# Sequantial_Cell_Switching.net
KiCad netlist of a schematic drawn in Altium Designer
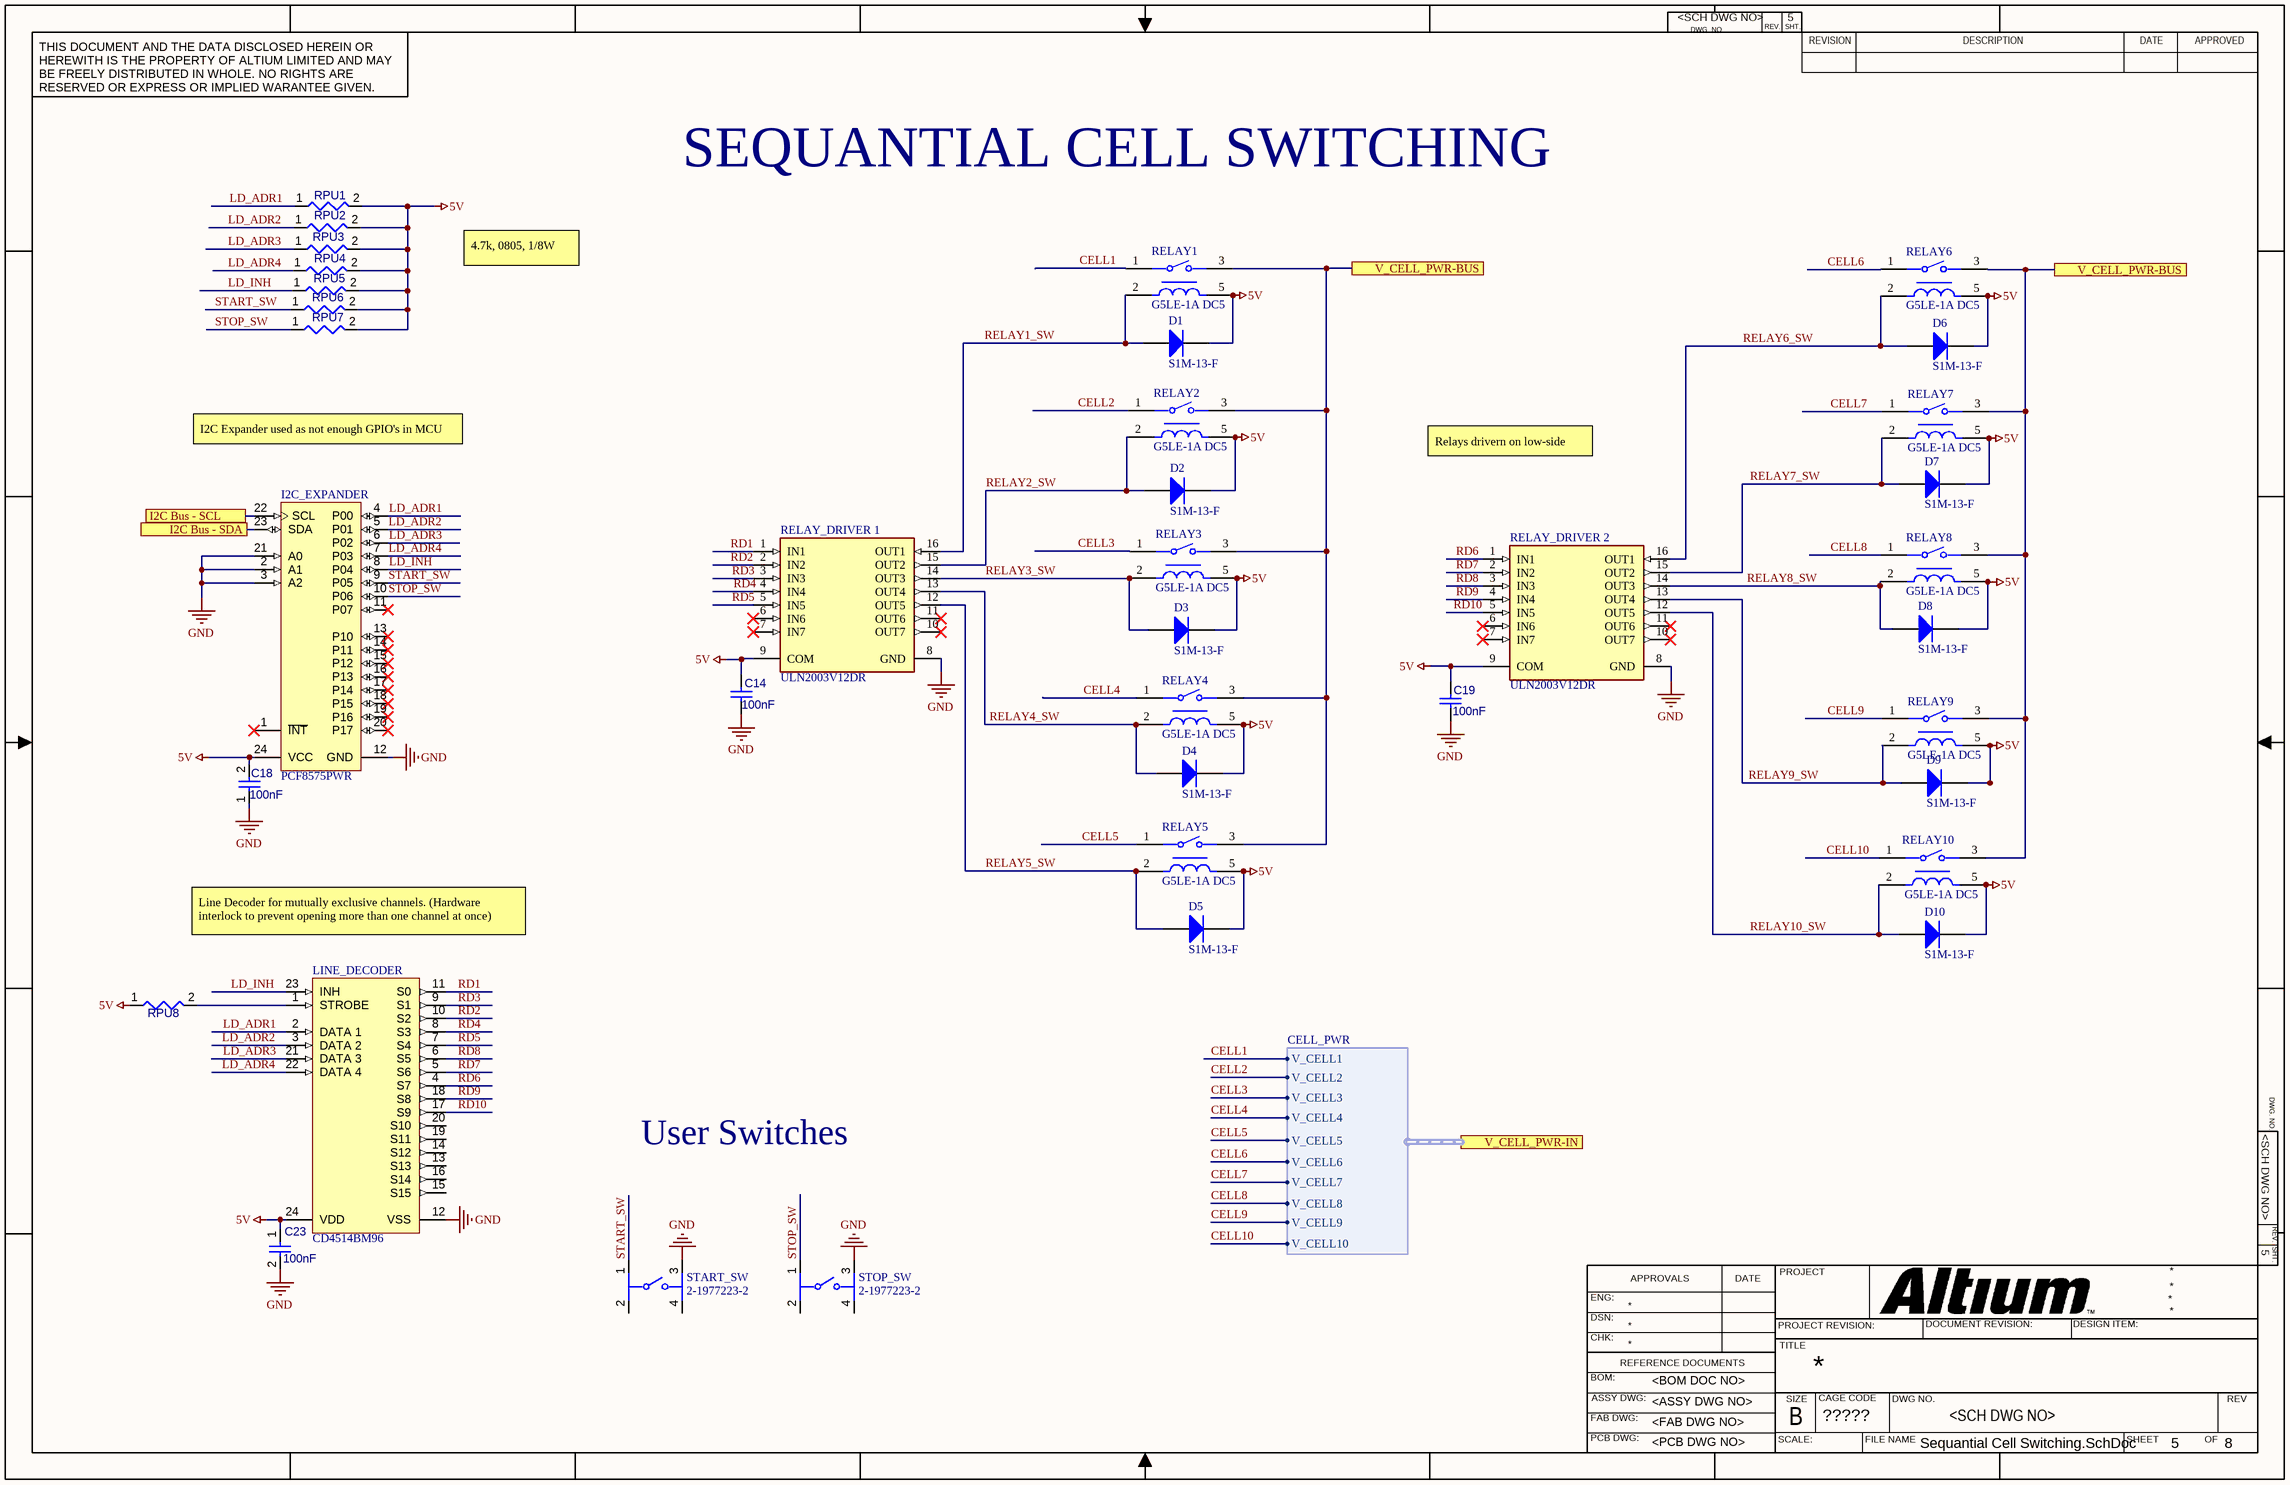
[diagram p0: Sequantial Cell Switching.SchDoc]

(export (version "E")
  (design (tool "Eeschema 10.0.6"))
  (components
    (comp (ref "C14")
      (value "100nF")
      (footprint "CAPC2013X95X50LL10T25")
      (description "Capacitor 100 nF +/-10% 50 V 0805")
      (fields (field (name "TOLERANCE") "10%"))
      (libsource (lib "") (part "CAP-NP-2_1"))
    )
    (comp (ref "C18")
      (value "100nF")
      (footprint "CAPC2013X95X50LL10T25")
      (description "Capacitor 100 nF +/-10% 50 V 0805")
      (fields (field (name "TOLERANCE") "10%"))
      (libsource (lib "gugan Sivakumar") (part "CAP-NP-2"))
    )
    (comp (ref "C19")
      (value "100nF")
      (footprint "CAPC2013X95X50LL10T25")
      (description "Capacitor 100 nF +/-10% 50 V 0805")
      (fields (field (name "TOLERANCE") "10%"))
      (libsource (lib "") (part "CAP-NP-2_1"))
    )
    (comp (ref "C23")
      (value "100nF")
      (footprint "CAPC2013X95X50LL10T25")
      (description "Capacitor 100 nF +/-10% 50 V 0805")
      (fields (field (name "TOLERANCE") "10%"))
      (libsource (lib "gugan Sivakumar") (part "CAP-NP-2"))
    )
    (comp (ref "D1")
      (value "S1M-13-F")
      (footprint "DIOD-S1M-13-F-SMA-2_V")
      (fields (field (name "MANUFACTURER") "Diodes Inc"))
      (libsource (lib "Altium Content Vault") (part "DIOD-D-A1K2-2"))
    )
    (comp (ref "D2")
      (value "S1M-13-F")
      (footprint "DIOD-S1M-13-F-SMA-2_V")
      (fields (field (name "MANUFACTURER") "Diodes Inc"))
      (libsource (lib "Altium Content Vault") (part "DIOD-D-A1K2-2"))
    )
    (comp (ref "D3")
      (value "S1M-13-F")
      (footprint "DIOD-S1M-13-F-SMA-2_V")
      (fields (field (name "MANUFACTURER") "Diodes Inc"))
      (libsource (lib "Altium Content Vault") (part "DIOD-D-A1K2-2"))
    )
    (comp (ref "D4")
      (value "S1M-13-F")
      (footprint "DIOD-S1M-13-F-SMA-2_V")
      (fields (field (name "MANUFACTURER") "Diodes Inc"))
      (libsource (lib "Altium Content Vault") (part "DIOD-D-A1K2-2"))
    )
    (comp (ref "D5")
      (value "S1M-13-F")
      (footprint "DIOD-S1M-13-F-SMA-2_V")
      (fields (field (name "MANUFACTURER") "Diodes Inc"))
      (libsource (lib "Altium Content Vault") (part "DIOD-D-A1K2-2"))
    )
    (comp (ref "D6")
      (value "S1M-13-F")
      (footprint "DIOD-S1M-13-F-SMA-2_V")
      (fields (field (name "MANUFACTURER") "Diodes Inc"))
      (libsource (lib "Altium Content Vault") (part "DIOD-D-A1K2-2"))
    )
    (comp (ref "D7")
      (value "S1M-13-F")
      (footprint "DIOD-S1M-13-F-SMA-2_V")
      (fields (field (name "MANUFACTURER") "Diodes Inc"))
      (libsource (lib "Altium Content Vault") (part "DIOD-D-A1K2-2"))
    )
    (comp (ref "D8")
      (value "S1M-13-F")
      (footprint "DIOD-S1M-13-F-SMA-2_V")
      (fields (field (name "MANUFACTURER") "Diodes Inc"))
      (libsource (lib "Altium Content Vault") (part "DIOD-D-A1K2-2"))
    )
    (comp (ref "D9")
      (value "S1M-13-F")
      (footprint "DIOD-S1M-13-F-SMA-2_V")
      (fields (field (name "MANUFACTURER") "Diodes Inc"))
      (libsource (lib "Altium Content Vault") (part "DIOD-D-A1K2-2"))
    )
    (comp (ref "D10")
      (value "S1M-13-F")
      (footprint "DIOD-S1M-13-F-SMA-2_V")
      (fields (field (name "MANUFACTURER") "Diodes Inc"))
      (libsource (lib "Altium Content Vault") (part "DIOD-D-A1K2-2"))
    )
    (comp (ref "I2C_EXPANDER")
      (value "PCF8575PWR")
      (footprint "PW0024A_L")
      (fields (field (name "MANUFACTURER") "Texas Instruments"))
      (libsource (lib "Altium Content Vault") (part "TI-PCF8575-TSSOP_PW-24"))
    )
    (comp (ref "LINE_DECODER")
      (value "CD4514BM96")
      (footprint "DW0024A_N")
      (description "CMOS 4-Bit Latch/4-to-16 Line Decoder with Output 'High' on Select, DW0024A, LARGE T&R")
      (fields
        (field (name "GENERIC PART NUMBER") "CD4514B")
        (field (name "MANUFACTURER") "Texas Instruments")
      )
      (libsource (lib "Altium Content Vault") (part "TI-CD451XB-24"))
    )
    (comp (ref "RELAY1")
      (value "G5LE-1A DC5")
      (footprint "FP-G5LE-1A_DC5-MFG")
      (description "RELAY GEN PURPOSE SPST 10A 5V")
      (libsource (lib "Altium Content Vault") (part "6e495d724dc645a58f977e2129b87ff"))
    )
    (comp (ref "RELAY2")
      (value "G5LE-1A DC5")
      (footprint "FP-G5LE-1A_DC5-MFG")
      (description "RELAY GEN PURPOSE SPST 10A 5V")
      (libsource (lib "Altium Content Vault") (part "6e495d724dc645a58f977e2129b87ff"))
    )
    (comp (ref "RELAY3")
      (value "G5LE-1A DC5")
      (footprint "FP-G5LE-1A_DC5-MFG")
      (description "RELAY GEN PURPOSE SPST 10A 5V")
      (libsource (lib "Altium Content Vault") (part "6e495d724dc645a58f977e2129b87ff"))
    )
    (comp (ref "RELAY4")
      (value "G5LE-1A DC5")
      (footprint "FP-G5LE-1A_DC5-MFG")
      (description "RELAY GEN PURPOSE SPST 10A 5V")
      (libsource (lib "Altium Content Vault") (part "6e495d724dc645a58f977e2129b87ff"))
    )
    (comp (ref "RELAY5")
      (value "G5LE-1A DC5")
      (footprint "FP-G5LE-1A_DC5-MFG")
      (description "RELAY GEN PURPOSE SPST 10A 5V")
      (libsource (lib "Altium Content Vault") (part "6e495d724dc645a58f977e2129b87ff"))
    )
    (comp (ref "RELAY6")
      (value "G5LE-1A DC5")
      (footprint "FP-G5LE-1A_DC5-MFG")
      (description "RELAY GEN PURPOSE SPST 10A 5V")
      (libsource (lib "Altium Content Vault") (part "6e495d724dc645a58f977e2129b87ff"))
    )
    (comp (ref "RELAY7")
      (value "G5LE-1A DC5")
      (footprint "FP-G5LE-1A_DC5-MFG")
      (description "RELAY GEN PURPOSE SPST 10A 5V")
      (libsource (lib "Altium Content Vault") (part "6e495d724dc645a58f977e2129b87ff"))
    )
    (comp (ref "RELAY8")
      (value "G5LE-1A DC5")
      (footprint "FP-G5LE-1A_DC5-MFG")
      (description "RELAY GEN PURPOSE SPST 10A 5V")
      (libsource (lib "Altium Content Vault") (part "6e495d724dc645a58f977e2129b87ff"))
    )
    (comp (ref "RELAY9")
      (value "G5LE-1A DC5")
      (footprint "FP-G5LE-1A_DC5-MFG")
      (description "RELAY GEN PURPOSE SPST 10A 5V")
      (libsource (lib "Altium Content Vault") (part "6e495d724dc645a58f977e2129b87ff"))
    )
    (comp (ref "RELAY10")
      (value "G5LE-1A DC5")
      (footprint "FP-G5LE-1A_DC5-MFG")
      (description "RELAY GEN PURPOSE SPST 10A 5V")
      (libsource (lib "Altium Content Vault") (part "6e495d724dc645a58f977e2129b87ff"))
    )
    (comp (ref "RELAY_DRIVER 1")
      (value "ULN2003V12DR")
      (footprint "FP-D0016A-MFG")
      (description "MOSFET 7CH 16SOIC")
      (libsource (lib "Altium Content Vault") (part "1bf5c18f3aeaca83cb90dec63c1b343"))
    )
    (comp (ref "RELAY_DRIVER 2")
      (value "ULN2003V12DR")
      (footprint "FP-D0016A-MFG")
      (description "MOSFET 7CH 16SOIC")
      (libsource (lib "Altium Content Vault") (part "1bf5c18f3aeaca83cb90dec63c1b343"))
    )
    (comp (ref "RPU1")
      (value "Resistor 4k7 +/-1% 0805 125 mW")
      (footprint "RESC2013X70X40ML20T20")
      (description "Chip Resistor, 4.7 KOhm, +/- 1%, 0.125 W, -55 to 155 degC, 0805 (2012 Metric)")
      (fields (field (name "TOLERANCE") "1%") (field (name "POWER") "125mW"))
      (libsource (lib "gugan Sivakumar") (part "RES-2"))
    )
    (comp (ref "RPU2")
      (value "Resistor 4k7 +/-1% 0805 125 mW")
      (footprint "RESC2013X70X40ML20T20")
      (description "Chip Resistor, 4.7 KOhm, +/- 1%, 0.125 W, -55 to 155 degC, 0805 (2012 Metric)")
      (fields (field (name "TOLERANCE") "1%") (field (name "POWER") "125mW"))
      (libsource (lib "gugan Sivakumar") (part "RES-2"))
    )
    (comp (ref "RPU3")
      (value "Resistor 4k7 +/-1% 0805 125 mW")
      (footprint "RESC2013X70X40ML20T20")
      (description "Chip Resistor, 4.7 KOhm, +/- 1%, 0.125 W, -55 to 155 degC, 0805 (2012 Metric)")
      (fields (field (name "TOLERANCE") "1%") (field (name "POWER") "125mW"))
      (libsource (lib "gugan Sivakumar") (part "RES-2"))
    )
    (comp (ref "RPU4")
      (value "Resistor 4k7 +/-1% 0805 125 mW")
      (footprint "RESC2013X70X40ML20T20")
      (description "Chip Resistor, 4.7 KOhm, +/- 1%, 0.125 W, -55 to 155 degC, 0805 (2012 Metric)")
      (fields (field (name "TOLERANCE") "1%") (field (name "POWER") "125mW"))
      (libsource (lib "gugan Sivakumar") (part "RES-2"))
    )
    (comp (ref "RPU5")
      (value "Resistor 4k7 +/-1% 0805 125 mW")
      (footprint "RESC2013X70X40ML20T20")
      (description "Chip Resistor, 4.7 KOhm, +/- 1%, 0.125 W, -55 to 155 degC, 0805 (2012 Metric)")
      (fields (field (name "TOLERANCE") "1%") (field (name "POWER") "125mW"))
      (libsource (lib "gugan Sivakumar") (part "RES-2"))
    )
    (comp (ref "RPU6")
      (value "Resistor 4k7 +/-1% 0805 125 mW")
      (footprint "RESC2013X70X40ML20T20")
      (description "Chip Resistor, 4.7 KOhm, +/- 1%, 0.125 W, -55 to 155 degC, 0805 (2012 Metric)")
      (fields (field (name "TOLERANCE") "1%") (field (name "POWER") "125mW"))
      (libsource (lib "gugan Sivakumar") (part "RES-2"))
    )
    (comp (ref "RPU7")
      (value "Resistor 4k7 +/-1% 0805 125 mW")
      (footprint "RESC2013X70X40ML20T20")
      (description "Chip Resistor, 4.7 KOhm, +/- 1%, 0.125 W, -55 to 155 degC, 0805 (2012 Metric)")
      (fields (field (name "TOLERANCE") "1%") (field (name "POWER") "125mW"))
      (libsource (lib "gugan Sivakumar") (part "RES-2"))
    )
    (comp (ref "RPU8")
      (value "Resistor 4k7 +/-1% 0805 125 mW")
      (footprint "RESC2013X70X40ML20T20")
      (description "Chip Resistor, 4.7 KOhm, +/- 1%, 0.125 W, -55 to 155 degC, 0805 (2012 Metric)")
      (fields (field (name "TOLERANCE") "1%") (field (name "POWER") "125mW"))
      (libsource (lib "gugan Sivakumar") (part "RES-2"))
    )
    (comp (ref "START_SW")
      (value "2-1977223-2")
      (footprint "FP-2-1977223-2-MFG")
      (description "SWITCH TACTILE SPST-NO 0.05A 24V")
      (libsource (lib "Altium Content Vault") (part "b8895f3f4cefb76e1819d2863dba89b"))
    )
    (comp (ref "STOP_SW")
      (value "2-1977223-2")
      (footprint "FP-2-1977223-2-MFG")
      (description "SWITCH TACTILE SPST-NO 0.05A 24V")
      (libsource (lib "Altium Content Vault") (part "b8895f3f4cefb76e1819d2863dba89b"))
    )
  )
  (nets
    (net (code "2") (name "/CELL1") (class "Default")
      (node (ref "RELAY1") (pin "1") (pinfunction "1_1") (pintype "passive"))
    )
    (net (code "3") (name "/CELL2") (class "Default")
      (node (ref "RELAY2") (pin "1") (pinfunction "1_1") (pintype "passive"))
    )
    (net (code "4") (name "/CELL3") (class "Default")
      (node (ref "RELAY3") (pin "1") (pinfunction "1_1") (pintype "passive"))
    )
    (net (code "5") (name "/CELL4") (class "Default")
      (node (ref "RELAY4") (pin "1") (pinfunction "1_1") (pintype "passive"))
    )
    (net (code "6") (name "/CELL5") (class "Default")
      (node (ref "RELAY5") (pin "1") (pinfunction "1_1") (pintype "passive"))
    )
    (net (code "7") (name "/CELL6") (class "Default")
      (node (ref "RELAY6") (pin "1") (pinfunction "1_1") (pintype "passive"))
    )
    (net (code "8") (name "/CELL7") (class "Default")
      (node (ref "RELAY7") (pin "1") (pinfunction "1_1") (pintype "passive"))
    )
    (net (code "9") (name "/CELL8") (class "Default")
      (node (ref "RELAY8") (pin "1") (pinfunction "1_1") (pintype "passive"))
    )
    (net (code "10") (name "/CELL9") (class "Default")
      (node (ref "RELAY9") (pin "1") (pinfunction "1_1") (pintype "passive"))
    )
    (net (code "11") (name "/CELL10") (class "Default")
      (node (ref "RELAY10") (pin "1") (pinfunction "1_1") (pintype "passive"))
    )
    (net (code "12") (name "/I2C Bus - SCL") (class "Default")
      (node (ref "I2C_EXPANDER") (pin "22") (pinfunction "SCL_22") (pintype "input"))
    )
    (net (code "13") (name "/I2C Bus - SDA") (class "Default")
      (node (ref "I2C_EXPANDER") (pin "23") (pinfunction "SDA_23") (pintype "bidirectional"))
    )
    (net (code "14") (name "/LD_ADR1") (class "Default")
      (node (ref "I2C_EXPANDER") (pin "4") (pinfunction "P00_4") (pintype "bidirectional"))
      (node (ref "LINE_DECODER") (pin "2") (pinfunction "DATA_1_2") (pintype "input"))
      (node (ref "RPU1") (pin "1") (pinfunction "1_1") (pintype "passive"))
    )
    (net (code "15") (name "/LD_ADR2") (class "Default")
      (node (ref "I2C_EXPANDER") (pin "5") (pinfunction "P01_5") (pintype "bidirectional"))
      (node (ref "LINE_DECODER") (pin "3") (pinfunction "DATA_2_3") (pintype "input"))
      (node (ref "RPU2") (pin "1") (pinfunction "1_1") (pintype "passive"))
    )
    (net (code "16") (name "/LD_ADR3") (class "Default")
      (node (ref "I2C_EXPANDER") (pin "6") (pinfunction "P02_6") (pintype "bidirectional"))
      (node (ref "LINE_DECODER") (pin "21") (pinfunction "DATA_3_21") (pintype "input"))
      (node (ref "RPU3") (pin "1") (pinfunction "1_1") (pintype "passive"))
    )
    (net (code "17") (name "/LD_ADR4") (class "Default")
      (node (ref "I2C_EXPANDER") (pin "7") (pinfunction "P03_7") (pintype "bidirectional"))
      (node (ref "LINE_DECODER") (pin "22") (pinfunction "DATA_4_22") (pintype "input"))
      (node (ref "RPU4") (pin "1") (pinfunction "1_1") (pintype "passive"))
    )
    (net (code "18") (name "/LD_INH") (class "Default")
      (node (ref "I2C_EXPANDER") (pin "8") (pinfunction "P04_8") (pintype "bidirectional"))
      (node (ref "LINE_DECODER") (pin "23") (pinfunction "INH_23") (pintype "input"))
      (node (ref "RPU5") (pin "1") (pinfunction "1_1") (pintype "passive"))
    )
    (net (code "19") (name "/RD1") (class "Default")
      (node (ref "LINE_DECODER") (pin "11") (pinfunction "S0_11") (pintype "output"))
      (node (ref "RELAY_DRIVER 1") (pin "1") (pinfunction "IN1_1") (pintype "input"))
    )
    (net (code "20") (name "/RD2") (class "Default")
      (node (ref "LINE_DECODER") (pin "10") (pinfunction "S2_10") (pintype "output"))
      (node (ref "RELAY_DRIVER 1") (pin "2") (pinfunction "IN2_2") (pintype "input"))
    )
    (net (code "21") (name "/RD3") (class "Default")
      (node (ref "LINE_DECODER") (pin "9") (pinfunction "S1_9") (pintype "output"))
      (node (ref "RELAY_DRIVER 1") (pin "3") (pinfunction "IN3_3") (pintype "input"))
    )
    (net (code "22") (name "/RD4") (class "Default")
      (node (ref "LINE_DECODER") (pin "8") (pinfunction "S3_8") (pintype "output"))
      (node (ref "RELAY_DRIVER 1") (pin "4") (pinfunction "IN4_4") (pintype "input"))
    )
    (net (code "23") (name "/RD5") (class "Default")
      (node (ref "LINE_DECODER") (pin "7") (pinfunction "S4_7") (pintype "output"))
      (node (ref "RELAY_DRIVER 1") (pin "5") (pinfunction "IN5_5") (pintype "input"))
    )
    (net (code "24") (name "/RD6") (class "Default")
      (node (ref "LINE_DECODER") (pin "4") (pinfunction "S7_4") (pintype "output"))
      (node (ref "RELAY_DRIVER 2") (pin "1") (pinfunction "IN1_1") (pintype "input"))
    )
    (net (code "25") (name "/RD7") (class "Default")
      (node (ref "LINE_DECODER") (pin "5") (pinfunction "S6_5") (pintype "output"))
      (node (ref "RELAY_DRIVER 2") (pin "2") (pinfunction "IN2_2") (pintype "input"))
    )
    (net (code "26") (name "/RD8") (class "Default")
      (node (ref "LINE_DECODER") (pin "6") (pinfunction "S5_6") (pintype "output"))
      (node (ref "RELAY_DRIVER 2") (pin "3") (pinfunction "IN3_3") (pintype "input"))
    )
    (net (code "27") (name "/RD9") (class "Default")
      (node (ref "LINE_DECODER") (pin "18") (pinfunction "S8_18") (pintype "output"))
      (node (ref "RELAY_DRIVER 2") (pin "4") (pinfunction "IN4_4") (pintype "input"))
    )
    (net (code "28") (name "/RD10") (class "Default")
      (node (ref "LINE_DECODER") (pin "17") (pinfunction "S9_17") (pintype "output"))
      (node (ref "RELAY_DRIVER 2") (pin "5") (pinfunction "IN5_5") (pintype "input"))
    )
    (net (code "29") (name "/RELAY1_SW") (class "Default")
      (node (ref "D1") (pin "1") (pinfunction "A_1") (pintype "passive"))
      (node (ref "RELAY1") (pin "2") (pinfunction "2_2") (pintype "passive"))
      (node (ref "RELAY_DRIVER 1") (pin "16") (pinfunction "OUT1_16") (pintype "input"))
    )
    (net (code "30") (name "/RELAY2_SW") (class "Default")
      (node (ref "D2") (pin "1") (pinfunction "A_1") (pintype "passive"))
      (node (ref "RELAY2") (pin "2") (pinfunction "2_2") (pintype "passive"))
      (node (ref "RELAY_DRIVER 1") (pin "15") (pinfunction "OUT2_15") (pintype "output"))
    )
    (net (code "31") (name "/RELAY3_SW") (class "Default")
      (node (ref "D3") (pin "1") (pinfunction "A_1") (pintype "passive"))
      (node (ref "RELAY3") (pin "2") (pinfunction "2_2") (pintype "passive"))
      (node (ref "RELAY_DRIVER 1") (pin "14") (pinfunction "OUT3_14") (pintype "output"))
    )
    (net (code "32") (name "/RELAY4_SW") (class "Default")
      (node (ref "D4") (pin "1") (pinfunction "A_1") (pintype "passive"))
      (node (ref "RELAY4") (pin "2") (pinfunction "2_2") (pintype "passive"))
      (node (ref "RELAY_DRIVER 1") (pin "13") (pinfunction "OUT4_13") (pintype "output"))
    )
    (net (code "33") (name "/RELAY5_SW") (class "Default")
      (node (ref "D5") (pin "1") (pinfunction "A_1") (pintype "passive"))
      (node (ref "RELAY5") (pin "2") (pinfunction "2_2") (pintype "passive"))
      (node (ref "RELAY_DRIVER 1") (pin "12") (pinfunction "OUT5_12") (pintype "output"))
    )
    (net (code "34") (name "/RELAY6_SW") (class "Default")
      (node (ref "D6") (pin "1") (pinfunction "A_1") (pintype "passive"))
      (node (ref "RELAY6") (pin "2") (pinfunction "2_2") (pintype "passive"))
      (node (ref "RELAY_DRIVER 2") (pin "16") (pinfunction "OUT1_16") (pintype "input"))
    )
    (net (code "35") (name "/RELAY7_SW") (class "Default")
      (node (ref "D7") (pin "1") (pinfunction "A_1") (pintype "passive"))
      (node (ref "RELAY7") (pin "2") (pinfunction "2_2") (pintype "passive"))
      (node (ref "RELAY_DRIVER 2") (pin "15") (pinfunction "OUT2_15") (pintype "output"))
    )
    (net (code "36") (name "/RELAY8_SW") (class "Default")
      (node (ref "D8") (pin "1") (pinfunction "A_1") (pintype "passive"))
      (node (ref "RELAY8") (pin "2") (pinfunction "2_2") (pintype "passive"))
      (node (ref "RELAY_DRIVER 2") (pin "14") (pinfunction "OUT3_14") (pintype "output"))
    )
    (net (code "37") (name "/RELAY9_SW") (class "Default")
      (node (ref "D9") (pin "1") (pinfunction "A_1") (pintype "passive"))
      (node (ref "RELAY9") (pin "2") (pinfunction "2_2") (pintype "passive"))
      (node (ref "RELAY_DRIVER 2") (pin "13") (pinfunction "OUT4_13") (pintype "output"))
    )
    (net (code "38") (name "/RELAY10_SW") (class "Default")
      (node (ref "D10") (pin "1") (pinfunction "A_1") (pintype "passive"))
      (node (ref "RELAY10") (pin "2") (pinfunction "2_2") (pintype "passive"))
      (node (ref "RELAY_DRIVER 2") (pin "12") (pinfunction "OUT5_12") (pintype "output"))
    )
    (net (code "39") (name "/START_SW") (class "Default")
      (node (ref "I2C_EXPANDER") (pin "9") (pinfunction "P05_9") (pintype "bidirectional"))
      (node (ref "RPU6") (pin "1") (pinfunction "1_1") (pintype "passive"))
      (node (ref "START_SW") (pin "1") (pinfunction "1_1") (pintype "passive"))
    )
    (net (code "40") (name "/STOP_SW") (class "Default")
      (node (ref "I2C_EXPANDER") (pin "10") (pinfunction "P06_10") (pintype "bidirectional"))
      (node (ref "RPU7") (pin "1") (pinfunction "1_1") (pintype "passive"))
      (node (ref "STOP_SW") (pin "1") (pinfunction "1_1") (pintype "passive"))
    )
    (net (code "41") (name "/V_CELL_PWR-BUS") (class "Default")
      (node (ref "RELAY1") (pin "3") (pinfunction "3_3") (pintype "passive"))
      (node (ref "RELAY10") (pin "3") (pinfunction "3_3") (pintype "passive"))
      (node (ref "RELAY2") (pin "3") (pinfunction "3_3") (pintype "passive"))
      (node (ref "RELAY3") (pin "3") (pinfunction "3_3") (pintype "passive"))
      (node (ref "RELAY4") (pin "3") (pinfunction "3_3") (pintype "passive"))
      (node (ref "RELAY5") (pin "3") (pinfunction "3_3") (pintype "passive"))
      (node (ref "RELAY6") (pin "3") (pinfunction "3_3") (pintype "passive"))
      (node (ref "RELAY7") (pin "3") (pinfunction "3_3") (pintype "passive"))
      (node (ref "RELAY8") (pin "3") (pinfunction "3_3") (pintype "passive"))
      (node (ref "RELAY9") (pin "3") (pinfunction "3_3") (pintype "passive"))
    )
    (net (code "43") (name "5V") (class "Default")
      (node (ref "C14") (pin "2") (pinfunction "2_2") (pintype "passive"))
      (node (ref "C18") (pin "2") (pinfunction "2_2") (pintype "passive"))
      (node (ref "C19") (pin "2") (pinfunction "2_2") (pintype "passive"))
      (node (ref "C23") (pin "1") (pinfunction "1_1") (pintype "passive"))
      (node (ref "D1") (pin "2") (pinfunction "K_2") (pintype "passive"))
      (node (ref "D10") (pin "2") (pinfunction "K_2") (pintype "passive"))
      (node (ref "D2") (pin "2") (pinfunction "K_2") (pintype "passive"))
      (node (ref "D3") (pin "2") (pinfunction "K_2") (pintype "passive"))
      (node (ref "D4") (pin "2") (pinfunction "K_2") (pintype "passive"))
      (node (ref "D5") (pin "2") (pinfunction "K_2") (pintype "passive"))
      (node (ref "D6") (pin "2") (pinfunction "K_2") (pintype "passive"))
      (node (ref "D7") (pin "2") (pinfunction "K_2") (pintype "passive"))
      (node (ref "D8") (pin "2") (pinfunction "K_2") (pintype "passive"))
      (node (ref "D9") (pin "2") (pinfunction "K_2") (pintype "passive"))
      (node (ref "I2C_EXPANDER") (pin "24") (pinfunction "VCC_24") (pintype "power_in"))
      (node (ref "LINE_DECODER") (pin "24") (pinfunction "VDD_24") (pintype "power_in"))
      (node (ref "RELAY1") (pin "5") (pinfunction "5_5") (pintype "passive"))
      (node (ref "RELAY10") (pin "5") (pinfunction "5_5") (pintype "passive"))
      (node (ref "RELAY2") (pin "5") (pinfunction "5_5") (pintype "passive"))
      (node (ref "RELAY3") (pin "5") (pinfunction "5_5") (pintype "passive"))
      (node (ref "RELAY4") (pin "5") (pinfunction "5_5") (pintype "passive"))
      (node (ref "RELAY5") (pin "5") (pinfunction "5_5") (pintype "passive"))
      (node (ref "RELAY6") (pin "5") (pinfunction "5_5") (pintype "passive"))
      (node (ref "RELAY7") (pin "5") (pinfunction "5_5") (pintype "passive"))
      (node (ref "RELAY8") (pin "5") (pinfunction "5_5") (pintype "passive"))
      (node (ref "RELAY9") (pin "5") (pinfunction "5_5") (pintype "passive"))
      (node (ref "RELAY_DRIVER 1") (pin "9") (pinfunction "COM_9") (pintype "passive"))
      (node (ref "RELAY_DRIVER 2") (pin "9") (pinfunction "COM_9") (pintype "passive"))
      (node (ref "RPU1") (pin "2") (pinfunction "2_2") (pintype "passive"))
      (node (ref "RPU2") (pin "2") (pinfunction "2_2") (pintype "passive"))
      (node (ref "RPU3") (pin "2") (pinfunction "2_2") (pintype "passive"))
      (node (ref "RPU4") (pin "2") (pinfunction "2_2") (pintype "passive"))
      (node (ref "RPU5") (pin "2") (pinfunction "2_2") (pintype "passive"))
      (node (ref "RPU6") (pin "2") (pinfunction "2_2") (pintype "passive"))
      (node (ref "RPU7") (pin "2") (pinfunction "2_2") (pintype "passive"))
      (node (ref "RPU8") (pin "1") (pinfunction "1_1") (pintype "passive"))
    )
    (net (code "44") (name "GND") (class "Default")
      (node (ref "C14") (pin "1") (pinfunction "1_1") (pintype "passive"))
      (node (ref "C18") (pin "1") (pinfunction "1_1") (pintype "passive"))
      (node (ref "C19") (pin "1") (pinfunction "1_1") (pintype "passive"))
      (node (ref "C23") (pin "2") (pinfunction "2_2") (pintype "passive"))
      (node (ref "I2C_EXPANDER") (pin "12") (pinfunction "GND_12") (pintype "power_in"))
      (node (ref "I2C_EXPANDER") (pin "2") (pinfunction "A1_2") (pintype "input"))
      (node (ref "I2C_EXPANDER") (pin "21") (pinfunction "A0_21") (pintype "input"))
      (node (ref "I2C_EXPANDER") (pin "3") (pinfunction "A2_3") (pintype "input"))
      (node (ref "LINE_DECODER") (pin "12") (pinfunction "VSS_12") (pintype "power_in"))
      (node (ref "RELAY_DRIVER 1") (pin "8") (pinfunction "GND_8") (pintype "power_in"))
      (node (ref "RELAY_DRIVER 2") (pin "8") (pinfunction "GND_8") (pintype "power_in"))
      (node (ref "START_SW") (pin "3") (pinfunction "3_3") (pintype "passive"))
      (node (ref "STOP_SW") (pin "3") (pinfunction "3_3") (pintype "passive"))
    )
    (net (code "45") (name "Net-(LINE_DECODER-STROBE)") (class "Default")
      (node (ref "LINE_DECODER") (pin "1") (pinfunction "STROBE_1") (pintype "input"))
      (node (ref "RPU8") (pin "2") (pinfunction "2_2") (pintype "passive"))
    )
    (net (code "46") (name "unconnected-(I2C_EXPANDER-P07-Pad11)") (class "Default")
      (node (ref "I2C_EXPANDER") (pin "11") (pinfunction "P07_11") (pintype "bidirectional+no_connect"))
    )
    (net (code "47") (name "unconnected-(I2C_EXPANDER-P10-Pad13)") (class "Default")
      (node (ref "I2C_EXPANDER") (pin "13") (pinfunction "P10_13") (pintype "bidirectional+no_connect"))
    )
    (net (code "48") (name "unconnected-(I2C_EXPANDER-P11-Pad14)") (class "Default")
      (node (ref "I2C_EXPANDER") (pin "14") (pinfunction "P11_14") (pintype "bidirectional+no_connect"))
    )
    (net (code "49") (name "unconnected-(I2C_EXPANDER-P12-Pad15)") (class "Default")
      (node (ref "I2C_EXPANDER") (pin "15") (pinfunction "P12_15") (pintype "bidirectional+no_connect"))
    )
    (net (code "50") (name "unconnected-(I2C_EXPANDER-P13-Pad16)") (class "Default")
      (node (ref "I2C_EXPANDER") (pin "16") (pinfunction "P13_16") (pintype "bidirectional+no_connect"))
    )
    (net (code "51") (name "unconnected-(I2C_EXPANDER-P14-Pad17)") (class "Default")
      (node (ref "I2C_EXPANDER") (pin "17") (pinfunction "P14_17") (pintype "bidirectional+no_connect"))
    )
    (net (code "52") (name "unconnected-(I2C_EXPANDER-P15-Pad18)") (class "Default")
      (node (ref "I2C_EXPANDER") (pin "18") (pinfunction "P15_18") (pintype "bidirectional+no_connect"))
    )
    (net (code "53") (name "unconnected-(I2C_EXPANDER-P16-Pad19)") (class "Default")
      (node (ref "I2C_EXPANDER") (pin "19") (pinfunction "P16_19") (pintype "bidirectional+no_connect"))
    )
    (net (code "54") (name "unconnected-(I2C_EXPANDER-P17-Pad20)") (class "Default")
      (node (ref "I2C_EXPANDER") (pin "20") (pinfunction "P17_20") (pintype "bidirectional+no_connect"))
    )
    (net (code "55") (name "unconnected-(I2C_EXPANDER-~{INT}-Pad1)") (class "Default")
      (node (ref "I2C_EXPANDER") (pin "1") (pinfunction "~{INT}_1") (pintype "open_collector+no_connect"))
    )
    (net (code "56") (name "unconnected-(LINE_DECODER-S10-Pad20)") (class "Default")
      (node (ref "LINE_DECODER") (pin "20") (pinfunction "S10_20") (pintype "output"))
    )
    (net (code "57") (name "unconnected-(LINE_DECODER-S11-Pad19)") (class "Default")
      (node (ref "LINE_DECODER") (pin "19") (pinfunction "S11_19") (pintype "output"))
    )
    (net (code "58") (name "unconnected-(LINE_DECODER-S12-Pad14)") (class "Default")
      (node (ref "LINE_DECODER") (pin "14") (pinfunction "S12_14") (pintype "output"))
    )
    (net (code "59") (name "unconnected-(LINE_DECODER-S13-Pad13)") (class "Default")
      (node (ref "LINE_DECODER") (pin "13") (pinfunction "S13_13") (pintype "output"))
    )
    (net (code "60") (name "unconnected-(LINE_DECODER-S14-Pad16)") (class "Default")
      (node (ref "LINE_DECODER") (pin "16") (pinfunction "S14_16") (pintype "output"))
    )
    (net (code "61") (name "unconnected-(LINE_DECODER-S15-Pad15)") (class "Default")
      (node (ref "LINE_DECODER") (pin "15") (pinfunction "S15_15") (pintype "output"))
    )
    (net (code "62") (name "unconnected-(RELAY_DRIVER 1-IN6-Pad6)") (class "Default")
      (node (ref "RELAY_DRIVER 1") (pin "6") (pinfunction "IN6_6") (pintype "input+no_connect"))
    )
    (net (code "63") (name "unconnected-(RELAY_DRIVER 1-IN7-Pad7)") (class "Default")
      (node (ref "RELAY_DRIVER 1") (pin "7") (pinfunction "IN7_7") (pintype "input+no_connect"))
    )
    (net (code "64") (name "unconnected-(RELAY_DRIVER 1-OUT6-Pad11)") (class "Default")
      (node (ref "RELAY_DRIVER 1") (pin "11") (pinfunction "OUT6_11") (pintype "output+no_connect"))
    )
    (net (code "65") (name "unconnected-(RELAY_DRIVER 1-OUT7-Pad10)") (class "Default")
      (node (ref "RELAY_DRIVER 1") (pin "10") (pinfunction "OUT7_10") (pintype "output+no_connect"))
    )
    (net (code "66") (name "unconnected-(RELAY_DRIVER 2-IN6-Pad6)") (class "Default")
      (node (ref "RELAY_DRIVER 2") (pin "6") (pinfunction "IN6_6") (pintype "input+no_connect"))
    )
    (net (code "67") (name "unconnected-(RELAY_DRIVER 2-IN7-Pad7)") (class "Default")
      (node (ref "RELAY_DRIVER 2") (pin "7") (pinfunction "IN7_7") (pintype "input+no_connect"))
    )
    (net (code "68") (name "unconnected-(RELAY_DRIVER 2-OUT6-Pad11)") (class "Default")
      (node (ref "RELAY_DRIVER 2") (pin "11") (pinfunction "OUT6_11") (pintype "output+no_connect"))
    )
    (net (code "69") (name "unconnected-(RELAY_DRIVER 2-OUT7-Pad10)") (class "Default")
      (node (ref "RELAY_DRIVER 2") (pin "10") (pinfunction "OUT7_10") (pintype "output+no_connect"))
    )
    (net (code "70") (name "unconnected-(START_SW-Pad2)") (class "Default")
      (node (ref "START_SW") (pin "2") (pinfunction "2_2") (pintype "passive"))
    )
    (net (code "71") (name "unconnected-(START_SW-Pad4)") (class "Default")
      (node (ref "START_SW") (pin "4") (pinfunction "4_4") (pintype "passive"))
    )
    (net (code "72") (name "unconnected-(STOP_SW-Pad2)") (class "Default")
      (node (ref "STOP_SW") (pin "2") (pinfunction "2_2") (pintype "passive"))
    )
    (net (code "73") (name "unconnected-(STOP_SW-Pad4)") (class "Default")
      (node (ref "STOP_SW") (pin "4") (pinfunction "4_4") (pintype "passive"))
    )
  )
)
